# 2channelrelaydriver_smd.net
KiCad netlist of a schematic drawn in EAGLE
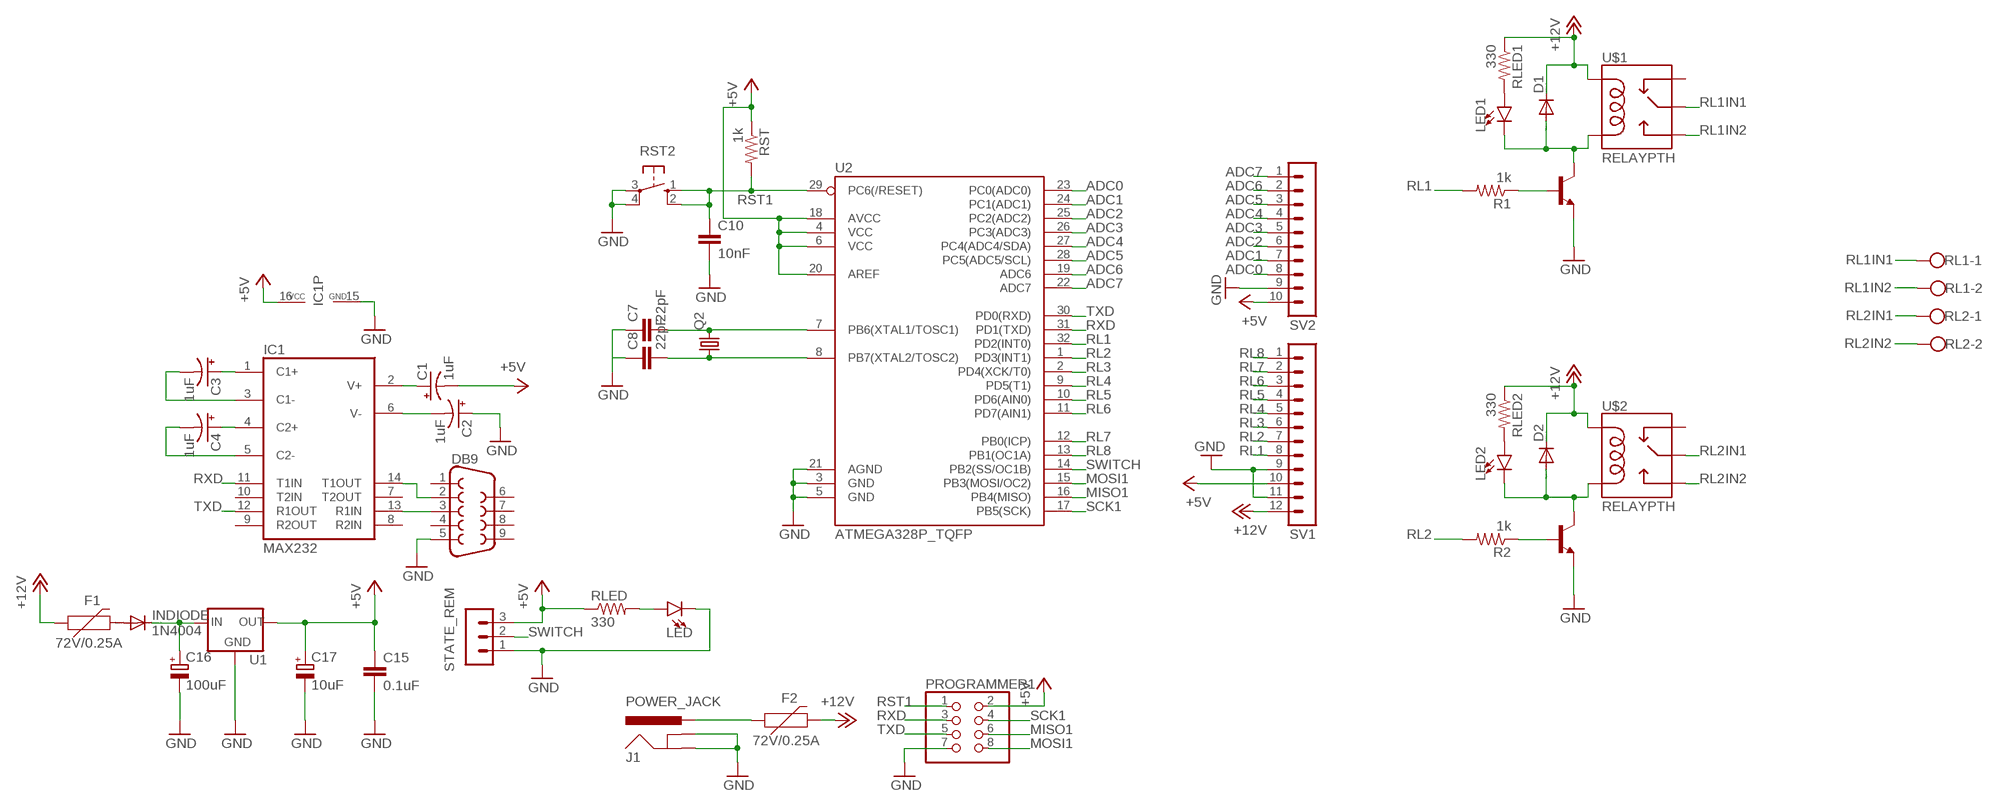
[diagram p0: schematic, sheet 1]

(export (version "E")
  (design (tool "Eeschema 10.0.6"))
  (components
    (comp (ref "C1")
      (value "1uF")
      (footprint "eagle-import:E2,5-6")
      (libsource (lib "eagle-import") (part "CPOL-USE2.5-6"))
    )
    (comp (ref "C2")
      (value "1uF")
      (footprint "eagle-import:E2,5-6")
      (libsource (lib "eagle-import") (part "CPOL-USE2.5-6"))
    )
    (comp (ref "C3")
      (value "1uF")
      (footprint "eagle-import:E2,5-6")
      (libsource (lib "eagle-import") (part "CPOL-USE2.5-6"))
    )
    (comp (ref "C4")
      (value "1uF")
      (footprint "eagle-import:E2,5-6")
      (libsource (lib "eagle-import") (part "CPOL-USE2.5-6"))
    )
    (comp (ref "C7")
      (value "22pF")
      (footprint "eagle-import:C1206")
      (libsource (lib "eagle-import") (part "C-EUC1206"))
    )
    (comp (ref "C8")
      (value "22pF")
      (footprint "eagle-import:C1206")
      (libsource (lib "eagle-import") (part "C-EUC1206"))
    )
    (comp (ref "C10")
      (value "10nF")
      (footprint "eagle-import:C1206")
      (libsource (lib "eagle-import") (part "C-EUC1206"))
    )
    (comp (ref "C15")
      (value "0.1uF")
      (footprint "eagle-import:C1206")
      (libsource (lib "eagle-import") (part "C-EUC1206"))
    )
    (comp (ref "C16")
      (value "100uF")
      (footprint "eagle-import:E2,5-6")
      (libsource (lib "eagle-import") (part "CPOL-EUE2.5-6"))
    )
    (comp (ref "C17")
      (value "10uF")
      (footprint "eagle-import:E2,5-6")
      (libsource (lib "eagle-import") (part "CPOL-EUE2.5-6"))
    )
    (comp (ref "D1")
      (value "1N4004")
      (footprint "eagle-import:DO41-10")
      (libsource (lib "eagle-import") (part "1N4004"))
    )
    (comp (ref "D2")
      (value "1N4004")
      (footprint "eagle-import:DO41-10")
      (libsource (lib "eagle-import") (part "1N4004"))
    )
    (comp (ref "DB9")
      (value "DB9FEMALE")
      (footprint "eagle-import:DB9")
      (libsource (lib "eagle-import") (part "DB9FEMALE"))
    )
    (comp (ref "F1")
      (value "72V/0.25A")
      (footprint "eagle-import:PTH")
      (libsource (lib "eagle-import") (part "PPTC_PTH"))
    )
    (comp (ref "F2")
      (value "72V/0.25A")
      (footprint "eagle-import:PTH")
      (libsource (lib "eagle-import") (part "PPTC_PTH"))
    )
    (comp (ref "IC1")
      (value "MAX232")
      (footprint "eagle-import:DIL16")
      (fields (field (name "MF") "MAXIM") (field (name "MPN") "MAX232ACPE+"))
      (libsource (lib "eagle-import") (part "MAX232"))
    )
    (comp (ref "INDIODE")
      (value "1N4004")
      (footprint "eagle-import:DO41-10")
      (libsource (lib "eagle-import") (part "1N4004"))
    )
    (comp (ref "J1")
      (value "POWER_JACK")
      (footprint "eagle-import:POWER_JACK_PTH")
      (libsource (lib "eagle-import") (part "POWER_JACK"))
    )
    (comp (ref "LED")
      (value "LED5MM")
      (footprint "eagle-import:LED_5MM")
      (libsource (lib "eagle-import") (part "LED5MM"))
    )
    (comp (ref "LED1")
      (value "LED5MM")
      (footprint "eagle-import:LED_5MM")
      (libsource (lib "eagle-import") (part "LED5MM"))
    )
    (comp (ref "LED2")
      (value "LED5MM")
      (footprint "eagle-import:LED_5MM")
      (libsource (lib "eagle-import") (part "LED5MM"))
    )
    (comp (ref "PROGRAMMER1")
      (value "PINHD-2X4")
      (footprint "eagle-import:2X04")
      (libsource (lib "eagle-import") (part "PINHD-2X4"))
    )
    (comp (ref "Q2")
      (value "CRYSTALHC49U70")
      (footprint "eagle-import:HC49U70")
      (libsource (lib "eagle-import") (part "CRYSTALHC49U70"))
    )
    (comp (ref "R1")
      (value "1k")
      (footprint "eagle-import:M1206")
      (libsource (lib "eagle-import") (part "R-US_M1206"))
    )
    (comp (ref "R2")
      (value "1k")
      (footprint "eagle-import:M1206")
      (libsource (lib "eagle-import") (part "R-US_M1206"))
    )
    (comp (ref "RL1")
      (value "W237-102")
      (footprint "eagle-import:W237-102")
      (fields (field (name "MPN") "237-102"))
      (libsource (lib "eagle-import") (part "W237-102"))
    )
    (comp (ref "RL2")
      (value "W237-102")
      (footprint "eagle-import:W237-102")
      (fields (field (name "MPN") "237-102"))
      (libsource (lib "eagle-import") (part "W237-102"))
    )
    (comp (ref "RLED")
      (value "330")
      (footprint "eagle-import:M1206")
      (libsource (lib "eagle-import") (part "R-US_M1206"))
    )
    (comp (ref "RLED1")
      (value "330")
      (footprint "eagle-import:M1206")
      (libsource (lib "eagle-import") (part "R-US_M1206"))
    )
    (comp (ref "RLED2")
      (value "330")
      (footprint "eagle-import:M1206")
      (libsource (lib "eagle-import") (part "R-US_M1206"))
    )
    (comp (ref "RST")
      (value "1k")
      (footprint "eagle-import:M1206")
      (libsource (lib "eagle-import") (part "R-US_M1206"))
    )
    (comp (ref "RST2")
      (value "10-XX")
      (footprint "eagle-import:B3F-10XX")
      (fields (field (name "MPN") "B3F-1000"))
      (libsource (lib "eagle-import") (part "10-XX"))
    )
    (comp (ref "STATE_REM")
      (value "MA03-1")
      (footprint "eagle-import:MA03-1")
      (libsource (lib "eagle-import") (part "MA03-1"))
    )
    (comp (ref "SV1")
      (value "MA12-1")
      (footprint "eagle-import:MA12-1")
      (libsource (lib "eagle-import") (part "MA12-1"))
    )
    (comp (ref "SV2")
      (value "MA10-1")
      (footprint "eagle-import:MA10-1")
      (libsource (lib "eagle-import") (part "MA10-1"))
    )
    (comp (ref "T1")
      (value "BC847")
      (footprint "eagle-import:SOT23")
      (libsource (lib "eagle-import") (part "BC847"))
    )
    (comp (ref "T2")
      (value "BC847")
      (footprint "eagle-import:SOT23")
      (libsource (lib "eagle-import") (part "BC847"))
    )
    (comp (ref "U$1")
      (value "RELAYPTH")
      (footprint "eagle-import:SRD-05VDC-SL-C")
      (libsource (lib "eagle-import") (part "RELAYPTH"))
    )
    (comp (ref "U$2")
      (value "RELAYPTH")
      (footprint "eagle-import:SRD-05VDC-SL-C")
      (libsource (lib "eagle-import") (part "RELAYPTH"))
    )
    (comp (ref "U1")
      (value "V_REG_78XXSIDE")
      (footprint "eagle-import:78XXL")
      (libsource (lib "eagle-import") (part "V_REG_78XXSIDE"))
    )
    (comp (ref "U2")
      (value "ATMEGA328P_TQFP")
      (footprint "eagle-import:TQFP32-08")
      (libsource (lib "eagle-import") (part "ATMEGA328P_TQFP"))
    )
  )
  (nets
    (net (code "1") (name "+5V") (class "Default")
      (node (ref "C1") (pin "-") (pinfunction "-_-") (pintype "passive"))
      (node (ref "C15") (pin "1") (pinfunction "1_1") (pintype "passive"))
      (node (ref "C17") (pin "+") (pinfunction "+_+") (pintype "passive"))
      (node (ref "IC1") (pin "16") (pinfunction "VCC_16") (pintype "power_in"))
      (node (ref "PROGRAMMER1") (pin "2") (pinfunction "2_2") (pintype "passive"))
      (node (ref "RLED") (pin "1") (pinfunction "1_1") (pintype "passive"))
      (node (ref "RST") (pin "1") (pinfunction "1_1") (pintype "passive"))
      (node (ref "STATE_REM") (pin "3") (pinfunction "3_3") (pintype "passive"))
      (node (ref "SV1") (pin "10") (pinfunction "10_10") (pintype "passive"))
      (node (ref "SV2") (pin "10") (pinfunction "10_10") (pintype "passive"))
      (node (ref "U1") (pin "OUT") (pinfunction "OUT_OUT") (pintype "passive"))
      (node (ref "U2") (pin "18") (pinfunction "AVCC_18") (pintype "bidirectional"))
      (node (ref "U2") (pin "20") (pinfunction "AREF_20") (pintype "bidirectional"))
      (node (ref "U2") (pin "4") (pinfunction "VCC_4") (pintype "bidirectional"))
      (node (ref "U2") (pin "6") (pinfunction "VCC_6") (pintype "bidirectional"))
    )
    (net (code "2") (name "+12V") (class "Default")
      (node (ref "D1") (pin "C") (pinfunction "C_C") (pintype "passive"))
      (node (ref "D2") (pin "C") (pinfunction "C_C") (pintype "passive"))
      (node (ref "F1") (pin "P$1") (pinfunction "1_P$1") (pintype "bidirectional"))
      (node (ref "F2") (pin "P$2") (pinfunction "2_P$2") (pintype "bidirectional"))
      (node (ref "RLED1") (pin "1") (pinfunction "1_1") (pintype "passive"))
      (node (ref "RLED2") (pin "1") (pinfunction "1_1") (pintype "passive"))
      (node (ref "SV1") (pin "12") (pinfunction "12_12") (pintype "passive"))
      (node (ref "U$1") (pin "COIL1") (pinfunction "COIL1_COIL1") (pintype "bidirectional"))
      (node (ref "U$2") (pin "COIL1") (pinfunction "COIL1_COIL1") (pintype "bidirectional"))
    )
    (net (code "3") (name "/ADC0") (class "Default")
      (node (ref "SV2") (pin "8") (pinfunction "8_8") (pintype "passive"))
      (node (ref "U2") (pin "23") (pinfunction "PC0(ADC0)_23") (pintype "bidirectional"))
    )
    (net (code "4") (name "/ADC1") (class "Default")
      (node (ref "SV2") (pin "7") (pinfunction "7_7") (pintype "passive"))
      (node (ref "U2") (pin "24") (pinfunction "PC1(ADC1)_24") (pintype "bidirectional"))
    )
    (net (code "5") (name "/ADC2") (class "Default")
      (node (ref "SV2") (pin "6") (pinfunction "6_6") (pintype "passive"))
      (node (ref "U2") (pin "25") (pinfunction "PC2(ADC2)_25") (pintype "bidirectional"))
    )
    (net (code "6") (name "/ADC3") (class "Default")
      (node (ref "SV2") (pin "5") (pinfunction "5_5") (pintype "passive"))
      (node (ref "U2") (pin "26") (pinfunction "PC3(ADC3)_26") (pintype "bidirectional"))
    )
    (net (code "7") (name "/ADC4") (class "Default")
      (node (ref "SV2") (pin "4") (pinfunction "4_4") (pintype "passive"))
      (node (ref "U2") (pin "27") (pinfunction "PC4(ADC4/SDA)_27") (pintype "bidirectional"))
    )
    (net (code "8") (name "/ADC5") (class "Default")
      (node (ref "SV2") (pin "3") (pinfunction "3_3") (pintype "passive"))
      (node (ref "U2") (pin "28") (pinfunction "PC5(ADC5/SCL)_28") (pintype "bidirectional"))
    )
    (net (code "9") (name "/ADC6") (class "Default")
      (node (ref "SV2") (pin "2") (pinfunction "2_2") (pintype "passive"))
      (node (ref "U2") (pin "19") (pinfunction "ADC6_19") (pintype "bidirectional"))
    )
    (net (code "10") (name "/ADC7") (class "Default")
      (node (ref "SV2") (pin "1") (pinfunction "1_1") (pintype "passive"))
      (node (ref "U2") (pin "22") (pinfunction "ADC7_22") (pintype "bidirectional"))
    )
    (net (code "11") (name "/MISO1") (class "Default")
      (node (ref "PROGRAMMER1") (pin "6") (pinfunction "6_6") (pintype "passive"))
      (node (ref "U2") (pin "16") (pinfunction "PB4(MISO)_16") (pintype "bidirectional"))
    )
    (net (code "12") (name "/MOSI1") (class "Default")
      (node (ref "PROGRAMMER1") (pin "8") (pinfunction "8_8") (pintype "passive"))
      (node (ref "U2") (pin "15") (pinfunction "PB3(MOSI/OC2)_15") (pintype "bidirectional"))
    )
    (net (code "13") (name "/RL1") (class "Default")
      (node (ref "R1") (pin "2") (pinfunction "2_2") (pintype "passive"))
      (node (ref "SV1") (pin "8") (pinfunction "8_8") (pintype "passive"))
      (node (ref "U2") (pin "32") (pinfunction "PD2(INT0)_32") (pintype "bidirectional"))
    )
    (net (code "14") (name "/RL1IN1") (class "Default")
      (node (ref "RL1") (pin "1") (pinfunction "KL_1") (pintype "passive"))
      (node (ref "U$1") (pin "SWCOMMON") (pinfunction "SWCOMMON_SWCOMMON") (pintype "bidirectional"))
    )
    (net (code "15") (name "/RL1IN2") (class "Default")
      (node (ref "RL1") (pin "2") (pinfunction "KL_2") (pintype "passive"))
      (node (ref "U$1") (pin "SWOPEN") (pinfunction "SWOPEN_SWOPEN") (pintype "bidirectional"))
    )
    (net (code "16") (name "/RL2") (class "Default")
      (node (ref "R2") (pin "2") (pinfunction "2_2") (pintype "passive"))
      (node (ref "SV1") (pin "7") (pinfunction "7_7") (pintype "passive"))
      (node (ref "U2") (pin "1") (pinfunction "PD3(INT1)_1") (pintype "bidirectional"))
    )
    (net (code "17") (name "/RL2IN1") (class "Default")
      (node (ref "RL2") (pin "1") (pinfunction "KL_1") (pintype "passive"))
      (node (ref "U$2") (pin "SWCOMMON") (pinfunction "SWCOMMON_SWCOMMON") (pintype "bidirectional"))
    )
    (net (code "18") (name "/RL2IN2") (class "Default")
      (node (ref "RL2") (pin "2") (pinfunction "KL_2") (pintype "passive"))
      (node (ref "U$2") (pin "SWOPEN") (pinfunction "SWOPEN_SWOPEN") (pintype "bidirectional"))
    )
    (net (code "19") (name "/RL3") (class "Default")
      (node (ref "SV1") (pin "6") (pinfunction "6_6") (pintype "passive"))
      (node (ref "U2") (pin "2") (pinfunction "PD4(XCK/T0)_2") (pintype "bidirectional"))
    )
    (net (code "20") (name "/RL4") (class "Default")
      (node (ref "SV1") (pin "5") (pinfunction "5_5") (pintype "passive"))
      (node (ref "U2") (pin "9") (pinfunction "PD5(T1)_9") (pintype "bidirectional"))
    )
    (net (code "21") (name "/RL5") (class "Default")
      (node (ref "SV1") (pin "4") (pinfunction "4_4") (pintype "passive"))
      (node (ref "U2") (pin "10") (pinfunction "PD6(AIN0)_10") (pintype "bidirectional"))
    )
    (net (code "22") (name "/RL6") (class "Default")
      (node (ref "SV1") (pin "3") (pinfunction "3_3") (pintype "passive"))
      (node (ref "U2") (pin "11") (pinfunction "PD7(AIN1)_11") (pintype "bidirectional"))
    )
    (net (code "23") (name "/RL7") (class "Default")
      (node (ref "SV1") (pin "2") (pinfunction "2_2") (pintype "passive"))
      (node (ref "U2") (pin "12") (pinfunction "PB0(ICP)_12") (pintype "bidirectional"))
    )
    (net (code "24") (name "/RL8") (class "Default")
      (node (ref "SV1") (pin "1") (pinfunction "1_1") (pintype "passive"))
      (node (ref "U2") (pin "13") (pinfunction "PB1(OC1A)_13") (pintype "bidirectional"))
    )
    (net (code "25") (name "/RST1") (class "Default")
      (node (ref "C10") (pin "1") (pinfunction "1_1") (pintype "passive"))
      (node (ref "PROGRAMMER1") (pin "1") (pinfunction "1_1") (pintype "passive"))
      (node (ref "RST") (pin "2") (pinfunction "2_2") (pintype "passive"))
      (node (ref "RST2") (pin "1") (pinfunction "S_1") (pintype "passive"))
      (node (ref "RST2") (pin "2") (pinfunction "S1_2") (pintype "passive"))
      (node (ref "U2") (pin "29") (pinfunction "PC6(/RESET)_29") (pintype "bidirectional"))
    )
    (net (code "26") (name "/RXD") (class "Default")
      (node (ref "IC1") (pin "11") (pinfunction "T1IN_11") (pintype "input"))
      (node (ref "PROGRAMMER1") (pin "3") (pinfunction "3_3") (pintype "passive"))
      (node (ref "U2") (pin "31") (pinfunction "PD1(TXD)_31") (pintype "bidirectional"))
    )
    (net (code "27") (name "/SCK1") (class "Default")
      (node (ref "PROGRAMMER1") (pin "4") (pinfunction "4_4") (pintype "passive"))
      (node (ref "U2") (pin "17") (pinfunction "PB5(SCK)_17") (pintype "bidirectional"))
    )
    (net (code "28") (name "/SWITCH") (class "Default")
      (node (ref "STATE_REM") (pin "2") (pinfunction "2_2") (pintype "passive"))
      (node (ref "U2") (pin "14") (pinfunction "PB2(SS/OC1B)_14") (pintype "bidirectional"))
    )
    (net (code "29") (name "/TXD") (class "Default")
      (node (ref "IC1") (pin "12") (pinfunction "R1OUT_12") (pintype "output"))
      (node (ref "PROGRAMMER1") (pin "5") (pinfunction "5_5") (pintype "passive"))
      (node (ref "U2") (pin "30") (pinfunction "PD0(RXD)_30") (pintype "bidirectional"))
    )
    (net (code "30") (name "GND") (class "Default")
      (node (ref "C10") (pin "2") (pinfunction "2_2") (pintype "passive"))
      (node (ref "C15") (pin "2") (pinfunction "2_2") (pintype "passive"))
      (node (ref "C16") (pin "-") (pinfunction "-_-") (pintype "passive"))
      (node (ref "C17") (pin "-") (pinfunction "-_-") (pintype "passive"))
      (node (ref "C2") (pin "+") (pinfunction "+_+") (pintype "passive"))
      (node (ref "C7") (pin "1") (pinfunction "1_1") (pintype "passive"))
      (node (ref "C8") (pin "1") (pinfunction "1_1") (pintype "passive"))
      (node (ref "DB9") (pin "5") (pinfunction "5_5") (pintype "passive"))
      (node (ref "IC1") (pin "15") (pinfunction "GND_15") (pintype "power_in"))
      (node (ref "J1") (pin "GND") (pinfunction "GND_GND") (pintype "bidirectional"))
      (node (ref "J1") (pin "GNDBREAK") (pinfunction "GNDBREAK_GNDBREAK") (pintype "bidirectional"))
      (node (ref "LED") (pin "K") (pinfunction "C_K") (pintype "passive"))
      (node (ref "PROGRAMMER1") (pin "7") (pinfunction "7_7") (pintype "passive"))
      (node (ref "RST2") (pin "3") (pinfunction "P_3") (pintype "passive"))
      (node (ref "RST2") (pin "4") (pinfunction "P1_4") (pintype "passive"))
      (node (ref "STATE_REM") (pin "1") (pinfunction "1_1") (pintype "passive"))
      (node (ref "SV1") (pin "11") (pinfunction "11_11") (pintype "passive"))
      (node (ref "SV1") (pin "9") (pinfunction "9_9") (pintype "passive"))
      (node (ref "SV2") (pin "9") (pinfunction "9_9") (pintype "passive"))
      (node (ref "T1") (pin "2") (pinfunction "E_2") (pintype "passive"))
      (node (ref "T2") (pin "2") (pinfunction "E_2") (pintype "passive"))
      (node (ref "U1") (pin "GND") (pinfunction "GND_GND") (pintype "input"))
      (node (ref "U2") (pin "21") (pinfunction "AGND_21") (pintype "bidirectional"))
      (node (ref "U2") (pin "3") (pinfunction "GND_3") (pintype "bidirectional"))
      (node (ref "U2") (pin "5") (pinfunction "GND_5") (pintype "bidirectional"))
    )
    (net (code "31") (name "Net-(C16-Pad+)") (class "Default")
      (node (ref "C16") (pin "+") (pinfunction "+_+") (pintype "passive"))
      (node (ref "INDIODE") (pin "C") (pinfunction "C_C") (pintype "passive"))
      (node (ref "U1") (pin "IN") (pinfunction "IN_IN") (pintype "input"))
    )
    (net (code "32") (name "Net-(F1-2)") (class "Default")
      (node (ref "F1") (pin "P$2") (pinfunction "2_P$2") (pintype "bidirectional"))
      (node (ref "INDIODE") (pin "A") (pinfunction "A_A") (pintype "passive"))
    )
    (net (code "33") (name "Net-(F2-1)") (class "Default")
      (node (ref "F2") (pin "P$1") (pinfunction "1_P$1") (pintype "bidirectional"))
      (node (ref "J1") (pin "PWR") (pinfunction "PWR_PWR") (pintype "bidirectional"))
    )
    (net (code "34") (name "Net-(IC1A-C1+)") (class "Default")
      (node (ref "C3") (pin "+") (pinfunction "+_+") (pintype "passive"))
      (node (ref "IC1") (pin "1") (pinfunction "C1+_1") (pintype "bidirectional"))
    )
    (net (code "35") (name "Net-(IC1A-C1-)") (class "Default")
      (node (ref "C3") (pin "-") (pinfunction "-_-") (pintype "passive"))
      (node (ref "IC1") (pin "3") (pinfunction "C1-_3") (pintype "bidirectional"))
    )
    (net (code "36") (name "Net-(IC1A-C2+)") (class "Default")
      (node (ref "C4") (pin "+") (pinfunction "+_+") (pintype "passive"))
      (node (ref "IC1") (pin "4") (pinfunction "C2+_4") (pintype "bidirectional"))
    )
    (net (code "37") (name "Net-(IC1A-C2-)") (class "Default")
      (node (ref "C4") (pin "-") (pinfunction "-_-") (pintype "passive"))
      (node (ref "IC1") (pin "5") (pinfunction "C2-_5") (pintype "bidirectional"))
    )
    (net (code "38") (name "Net-(IC1A-R1IN)") (class "Default")
      (node (ref "DB9") (pin "3") (pinfunction "3_3") (pintype "passive"))
      (node (ref "IC1") (pin "13") (pinfunction "R1IN_13") (pintype "input"))
    )
    (net (code "39") (name "Net-(IC1A-T1OUT)") (class "Default")
      (node (ref "DB9") (pin "2") (pinfunction "2_2") (pintype "passive"))
      (node (ref "IC1") (pin "14") (pinfunction "T1OUT_14") (pintype "output"))
    )
    (net (code "40") (name "Net-(IC1A-V+)") (class "Default")
      (node (ref "C1") (pin "+") (pinfunction "+_+") (pintype "passive"))
      (node (ref "IC1") (pin "2") (pinfunction "V+_2") (pintype "bidirectional"))
    )
    (net (code "41") (name "Net-(IC1A-V-)") (class "Default")
      (node (ref "C2") (pin "-") (pinfunction "-_-") (pintype "passive"))
      (node (ref "IC1") (pin "6") (pinfunction "V-_6") (pintype "bidirectional"))
    )
    (net (code "42") (name "Net-(LED-PadA)") (class "Default")
      (node (ref "LED") (pin "A") (pinfunction "A_A") (pintype "passive"))
      (node (ref "RLED") (pin "2") (pinfunction "2_2") (pintype "passive"))
    )
    (net (code "43") (name "Net-(LED1-C)") (class "Default")
      (node (ref "D1") (pin "A") (pinfunction "A_A") (pintype "passive"))
      (node (ref "LED1") (pin "K") (pinfunction "C_K") (pintype "passive"))
      (node (ref "T1") (pin "3") (pinfunction "C_3") (pintype "passive"))
      (node (ref "U$1") (pin "COIL0") (pinfunction "COIL0_COIL0") (pintype "bidirectional"))
    )
    (net (code "44") (name "Net-(LED1-PadA)") (class "Default")
      (node (ref "LED1") (pin "A") (pinfunction "A_A") (pintype "passive"))
      (node (ref "RLED1") (pin "2") (pinfunction "2_2") (pintype "passive"))
    )
    (net (code "45") (name "Net-(LED2-C)") (class "Default")
      (node (ref "D2") (pin "A") (pinfunction "A_A") (pintype "passive"))
      (node (ref "LED2") (pin "K") (pinfunction "C_K") (pintype "passive"))
      (node (ref "T2") (pin "3") (pinfunction "C_3") (pintype "passive"))
      (node (ref "U$2") (pin "COIL0") (pinfunction "COIL0_COIL0") (pintype "bidirectional"))
    )
    (net (code "46") (name "Net-(LED2-PadA)") (class "Default")
      (node (ref "LED2") (pin "A") (pinfunction "A_A") (pintype "passive"))
      (node (ref "RLED2") (pin "2") (pinfunction "2_2") (pintype "passive"))
    )
    (net (code "47") (name "Net-(T1-B)") (class "Default")
      (node (ref "R1") (pin "1") (pinfunction "1_1") (pintype "passive"))
      (node (ref "T1") (pin "1") (pinfunction "B_1") (pintype "passive"))
    )
    (net (code "48") (name "Net-(T2-B)") (class "Default")
      (node (ref "R2") (pin "1") (pinfunction "1_1") (pintype "passive"))
      (node (ref "T2") (pin "1") (pinfunction "B_1") (pintype "passive"))
    )
    (net (code "49") (name "Net-(U2-PB6(XTAL1{slash}TOSC1))") (class "Default")
      (node (ref "C7") (pin "2") (pinfunction "2_2") (pintype "passive"))
      (node (ref "Q2") (pin "2") (pinfunction "2_2") (pintype "passive"))
      (node (ref "U2") (pin "7") (pinfunction "PB6(XTAL1/TOSC1)_7") (pintype "bidirectional"))
    )
    (net (code "50") (name "Net-(U2-PB7(XTAL2{slash}TOSC2))") (class "Default")
      (node (ref "C8") (pin "2") (pinfunction "2_2") (pintype "passive"))
      (node (ref "Q2") (pin "1") (pinfunction "1_1") (pintype "passive"))
      (node (ref "U2") (pin "8") (pinfunction "PB7(XTAL2/TOSC2)_8") (pintype "bidirectional"))
    )
    (net (code "51") (name "unconnected-(DB9-Pad1)") (class "Default")
      (node (ref "DB9") (pin "1") (pinfunction "1_1") (pintype "passive"))
    )
    (net (code "52") (name "unconnected-(DB9-Pad4)") (class "Default")
      (node (ref "DB9") (pin "4") (pinfunction "4_4") (pintype "passive"))
    )
    (net (code "53") (name "unconnected-(DB9-Pad6)") (class "Default")
      (node (ref "DB9") (pin "6") (pinfunction "6_6") (pintype "passive"))
    )
    (net (code "54") (name "unconnected-(DB9-Pad7)") (class "Default")
      (node (ref "DB9") (pin "7") (pinfunction "7_7") (pintype "passive"))
    )
    (net (code "55") (name "unconnected-(DB9-Pad8)") (class "Default")
      (node (ref "DB9") (pin "8") (pinfunction "8_8") (pintype "passive"))
    )
    (net (code "56") (name "unconnected-(DB9-Pad9)") (class "Default")
      (node (ref "DB9") (pin "9") (pinfunction "9_9") (pintype "passive"))
    )
    (net (code "57") (name "unconnected-(IC1A-R2IN-Pad8)") (class "Default")
      (node (ref "IC1") (pin "8") (pinfunction "R2IN_8") (pintype "input"))
    )
    (net (code "58") (name "unconnected-(IC1A-R2OUT-Pad9)") (class "Default")
      (node (ref "IC1") (pin "9") (pinfunction "R2OUT_9") (pintype "output"))
    )
    (net (code "59") (name "unconnected-(IC1A-T2IN-Pad10)") (class "Default")
      (node (ref "IC1") (pin "10") (pinfunction "T2IN_10") (pintype "input"))
    )
    (net (code "60") (name "unconnected-(IC1A-T2OUT-Pad7)") (class "Default")
      (node (ref "IC1") (pin "7") (pinfunction "T2OUT_7") (pintype "output"))
    )
    (net (code "61") (name "unconnected-(U$1-SWCLOSE-PadSWCLOSED)") (class "Default")
      (node (ref "U$1") (pin "SWCLOSED") (pinfunction "SWCLOSE_SWCLOSED") (pintype "bidirectional"))
    )
    (net (code "62") (name "unconnected-(U$2-SWCLOSE-PadSWCLOSED)") (class "Default")
      (node (ref "U$2") (pin "SWCLOSED") (pinfunction "SWCLOSE_SWCLOSED") (pintype "bidirectional"))
    )
  )
)
